# 17_FLOW_Sensor.net
KiCad netlist of a schematic drawn in Altium Designer
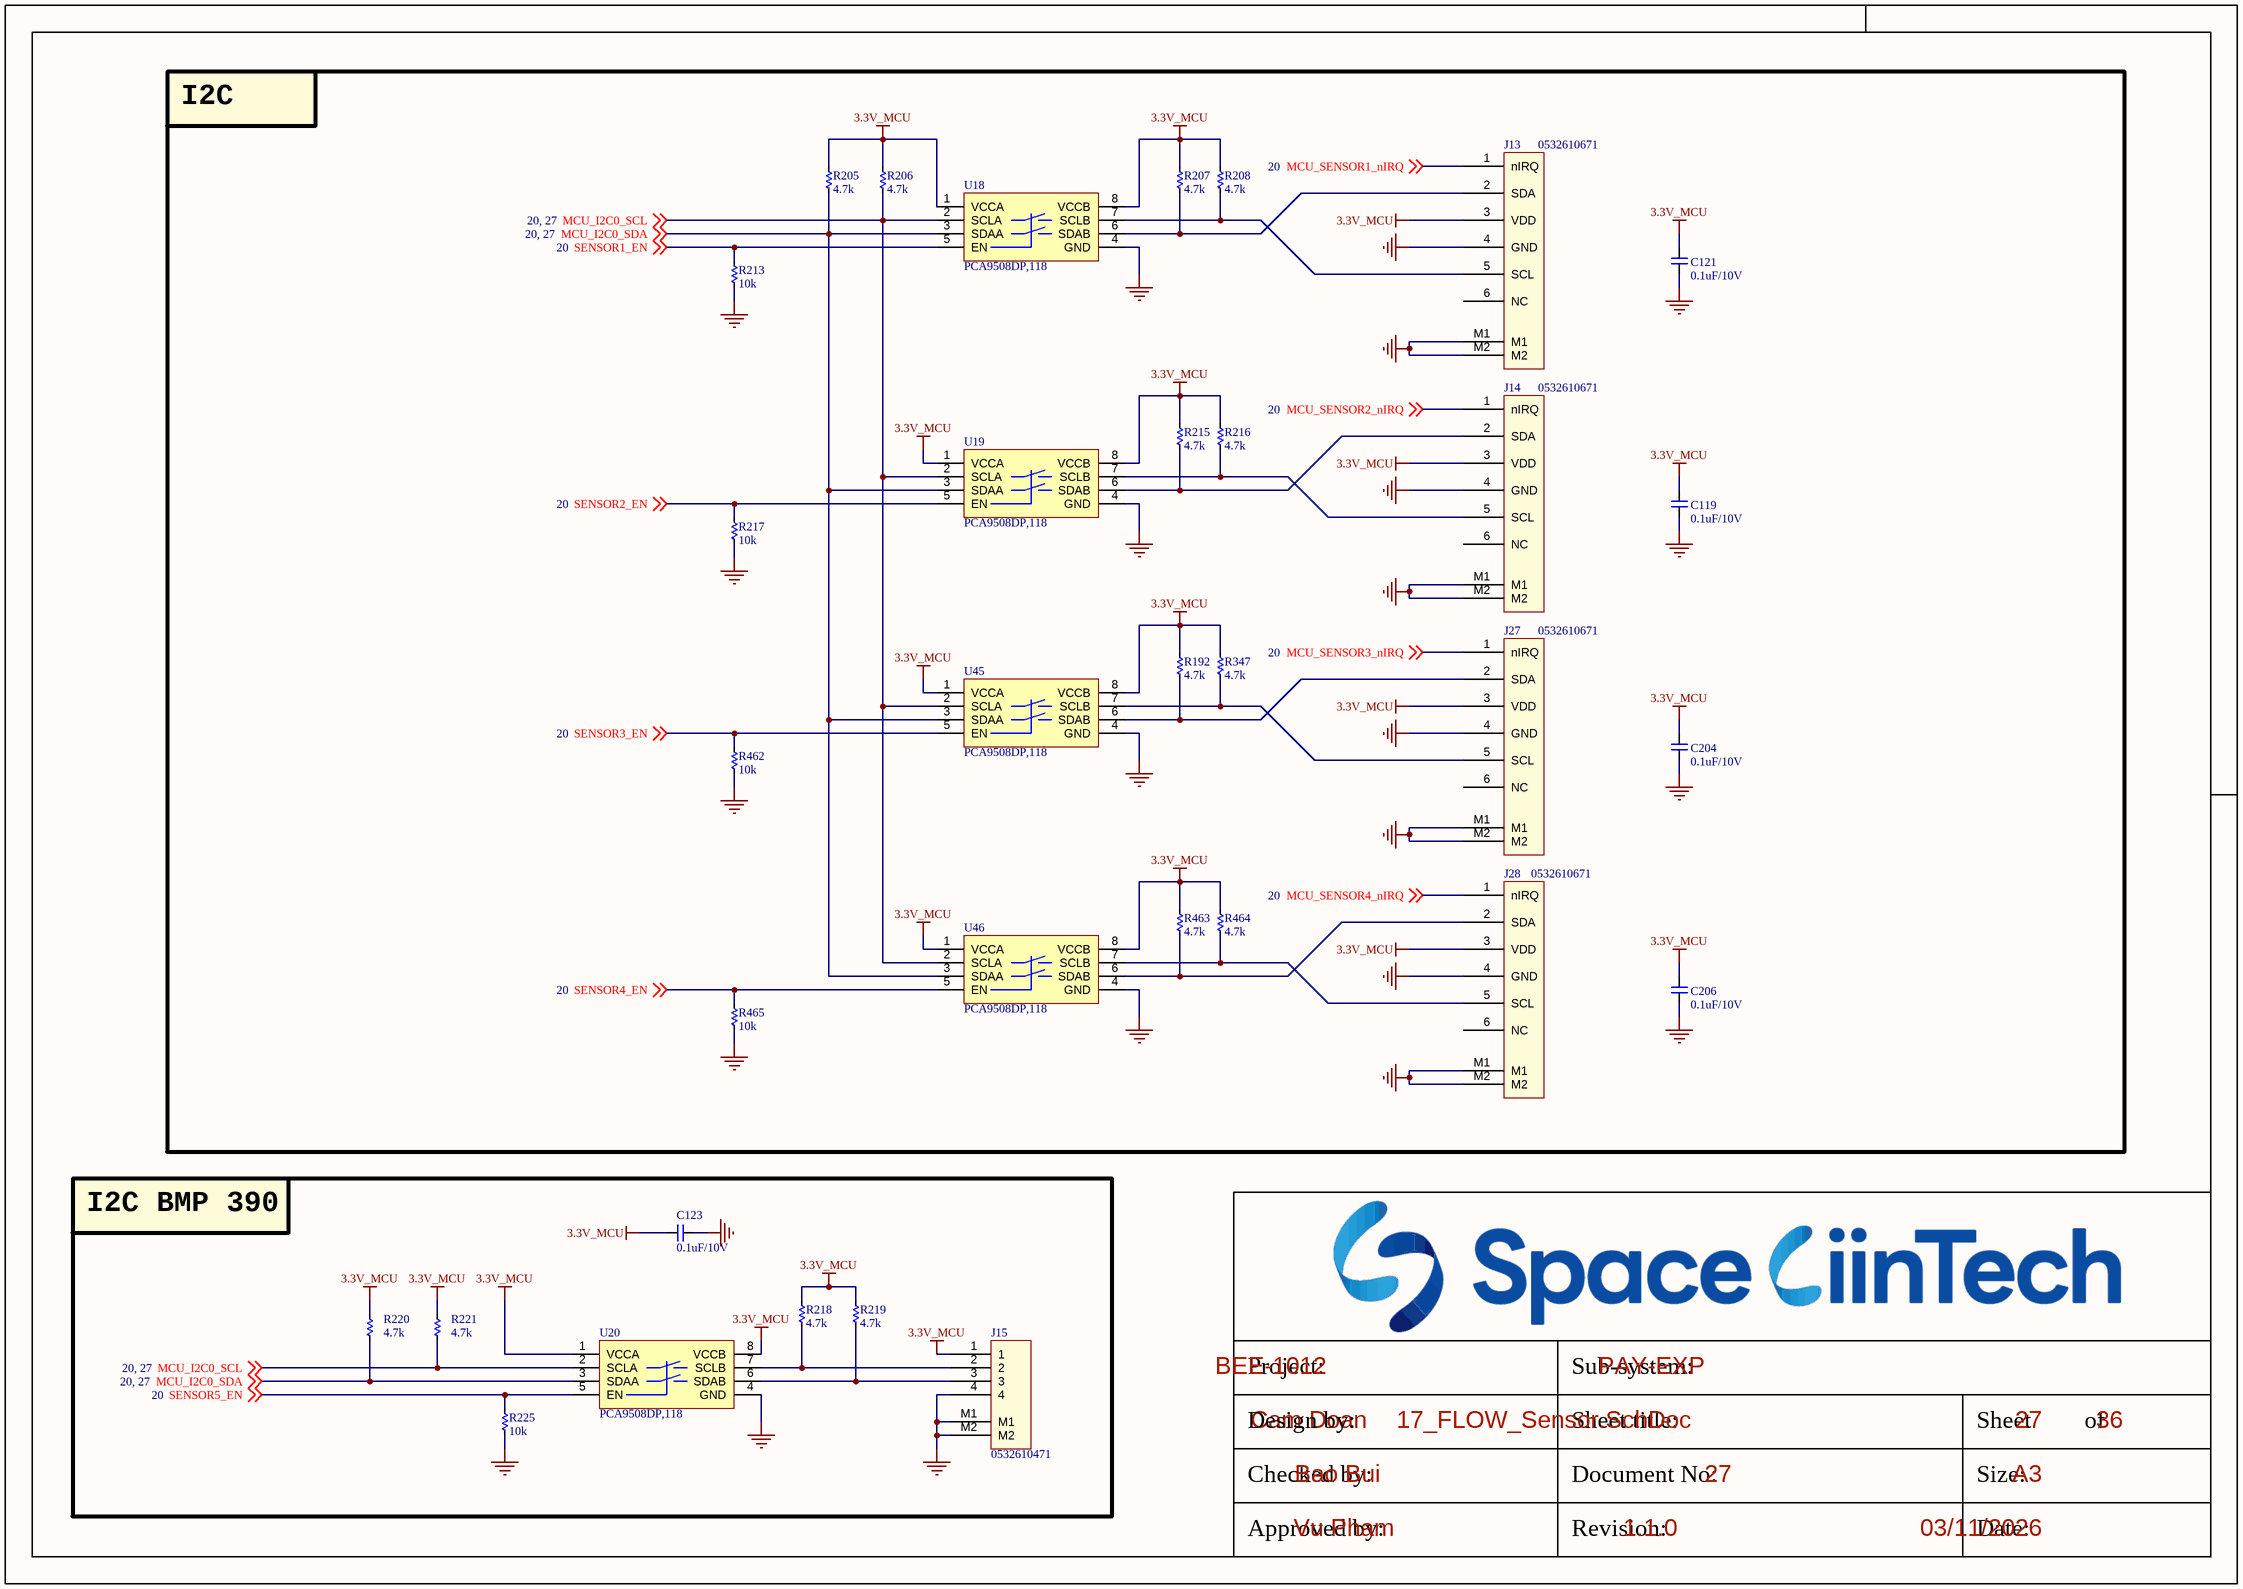
[diagram p0: 17_FLOW_Sensor.SchDoc]

(export (version "E")
  (design (tool "Eeschema 10.0.6"))
  (components
    (comp (ref "C119")
      (value "0.1uF/10V")
      (footprint "CAP_C_1005X60")
      (description "CAP")
      (libsource (lib "LABLIB") (part "_CAP_C_2"))
    )
    (comp (ref "C121")
      (value "0.1uF/10V")
      (footprint "CAP_C_1005X60")
      (description "CAP")
      (libsource (lib "LABLIB") (part "_CAP_C_2"))
    )
    (comp (ref "C123")
      (value "0.1uF/10V")
      (footprint "CAP_C_1005X60")
      (description "CAP")
      (libsource (lib "LABLIB") (part "_CAP_C_2"))
    )
    (comp (ref "C204")
      (value "0.1uF/10V")
      (footprint "CAP_C_1005X60")
      (description "CAP")
      (libsource (lib "LABLIB") (part "_CAP_C_2"))
    )
    (comp (ref "C206")
      (value "0.1uF/10V")
      (footprint "CAP_C_1005X60")
      (description "CAP")
      (libsource (lib "LABLIB") (part "_CAP_C_2"))
    )
    (comp (ref "J13")
      (value "0532610671")
      (footprint "MOLEX_0532610671")
      (libsource (lib "LABLIB") (part "FLOW_SENSOR"))
    )
    (comp (ref "J14")
      (value "0532610671")
      (footprint "MOLEX_0532610671")
      (libsource (lib "LABLIB") (part "FLOW_SENSOR"))
    )
    (comp (ref "J15")
      (value "0532610471")
      (footprint "MOLEX_0532610471")
      (libsource (lib "LABLIB") (part "Header 4x1_2M"))
    )
    (comp (ref "J27")
      (value "0532610671")
      (footprint "MOLEX_0532610671")
      (libsource (lib "LABLIB") (part "FLOW_SENSOR"))
    )
    (comp (ref "J28")
      (value "0532610671")
      (footprint "MOLEX_0532610671")
      (libsource (lib "LABLIB") (part "FLOW_SENSOR"))
    )
    (comp (ref "R192")
      (value "4.7k")
      (footprint "RES_C_1005X40")
      (description "RES")
      (libsource (lib "LABLIB") (part "_RES_B_2"))
    )
    (comp (ref "R205")
      (value "4.7k")
      (footprint "RES_C_1005X40")
      (description "RES")
      (libsource (lib "LABLIB") (part "_RES_B_2"))
    )
    (comp (ref "R206")
      (value "4.7k")
      (footprint "RES_C_1005X40")
      (description "RES")
      (libsource (lib "LABLIB") (part "_RES_B_2"))
    )
    (comp (ref "R207")
      (value "4.7k")
      (footprint "RES_C_1005X40")
      (description "RES")
      (libsource (lib "LABLIB") (part "_RES_B_2"))
    )
    (comp (ref "R208")
      (value "4.7k")
      (footprint "RES_C_1005X40")
      (description "RES")
      (libsource (lib "LABLIB") (part "_RES_B_2"))
    )
    (comp (ref "R213")
      (value "10k")
      (footprint "RES_C_1005X40")
      (description "RES")
      (libsource (lib "LABLIB") (part "_RES_B_2"))
    )
    (comp (ref "R215")
      (value "4.7k")
      (footprint "RES_C_1005X40")
      (description "RES")
      (libsource (lib "LABLIB") (part "_RES_B_2"))
    )
    (comp (ref "R216")
      (value "4.7k")
      (footprint "RES_C_1005X40")
      (description "RES")
      (libsource (lib "LABLIB") (part "_RES_B_2"))
    )
    (comp (ref "R217")
      (value "10k")
      (footprint "RES_C_1005X40")
      (description "RES")
      (libsource (lib "LABLIB") (part "_RES_B_2"))
    )
    (comp (ref "R218")
      (value "4.7k")
      (footprint "RES_C_1005X40")
      (description "RES")
      (libsource (lib "LABLIB") (part "_RES_B_2"))
    )
    (comp (ref "R219")
      (value "4.7k")
      (footprint "RES_C_1005X40")
      (description "RES")
      (libsource (lib "LABLIB") (part "_RES_B_2"))
    )
    (comp (ref "R220")
      (value "4.7k")
      (footprint "RES_C_1005X40")
      (description "RES")
      (libsource (lib "LABLIB") (part "_RES_B_2"))
    )
    (comp (ref "R221")
      (value "4.7k")
      (footprint "RES_C_1005X40")
      (description "RES")
      (libsource (lib "LABLIB") (part "_RES_B_2"))
    )
    (comp (ref "R225")
      (value "10k")
      (footprint "RES_C_1005X40")
      (description "RES")
      (libsource (lib "LABLIB") (part "_RES_B_2"))
    )
    (comp (ref "R347")
      (value "4.7k")
      (footprint "RES_C_1005X40")
      (description "RES")
      (libsource (lib "LABLIB") (part "_RES_B_2"))
    )
    (comp (ref "R462")
      (value "10k")
      (footprint "RES_C_1005X40")
      (description "RES")
      (libsource (lib "LABLIB") (part "_RES_B_2"))
    )
    (comp (ref "R463")
      (value "4.7k")
      (footprint "RES_C_1005X40")
      (description "RES")
      (libsource (lib "LABLIB") (part "_RES_B_2"))
    )
    (comp (ref "R464")
      (value "4.7k")
      (footprint "RES_C_1005X40")
      (description "RES")
      (libsource (lib "LABLIB") (part "_RES_B_2"))
    )
    (comp (ref "R465")
      (value "10k")
      (footprint "RES_C_1005X40")
      (description "RES")
      (libsource (lib "LABLIB") (part "_RES_B_2"))
    )
    (comp (ref "U18")
      (value "PCA9508DP,118")
      (footprint "TSOP8")
      (libsource (lib "EXP_HW_V3") (part "PCA9508DP,118"))
    )
    (comp (ref "U19")
      (value "PCA9508DP,118")
      (footprint "TSOP8")
      (libsource (lib "EXP_HW_V3") (part "PCA9508DP,118"))
    )
    (comp (ref "U20")
      (value "PCA9508DP,118")
      (footprint "TSOP8")
      (libsource (lib "EXP_HW_V3") (part "PCA9508DP,118"))
    )
    (comp (ref "U45")
      (value "PCA9508DP,118")
      (footprint "TSOP8")
      (libsource (lib "EXP_HW_V3") (part "PCA9508DP,118"))
    )
    (comp (ref "U46")
      (value "PCA9508DP,118")
      (footprint "TSOP8")
      (libsource (lib "EXP_HW_V3") (part "PCA9508DP,118"))
    )
  )
  (nets
    (net (code "1") (name "3.3V_MCU") (class "Default")
      (node (ref "C119") (pin "2") (pinfunction "2_2") (pintype "passive"))
      (node (ref "C121") (pin "2") (pinfunction "2_2") (pintype "passive"))
      (node (ref "C123") (pin "2") (pinfunction "2_2") (pintype "passive"))
      (node (ref "C204") (pin "2") (pinfunction "2_2") (pintype "passive"))
      (node (ref "C206") (pin "2") (pinfunction "2_2") (pintype "passive"))
      (node (ref "J13") (pin "3") (pinfunction "VDD_3") (pintype "passive"))
      (node (ref "J14") (pin "3") (pinfunction "VDD_3") (pintype "passive"))
      (node (ref "J15") (pin "1") (pinfunction "1_1") (pintype "passive"))
      (node (ref "J27") (pin "3") (pinfunction "VDD_3") (pintype "passive"))
      (node (ref "J28") (pin "3") (pinfunction "VDD_3") (pintype "passive"))
      (node (ref "R192") (pin "1") (pinfunction "1_1") (pintype "passive"))
      (node (ref "R205") (pin "1") (pinfunction "1_1") (pintype "passive"))
      (node (ref "R206") (pin "1") (pinfunction "1_1") (pintype "passive"))
      (node (ref "R207") (pin "1") (pinfunction "1_1") (pintype "passive"))
      (node (ref "R208") (pin "1") (pinfunction "1_1") (pintype "passive"))
      (node (ref "R215") (pin "1") (pinfunction "1_1") (pintype "passive"))
      (node (ref "R216") (pin "1") (pinfunction "1_1") (pintype "passive"))
      (node (ref "R218") (pin "1") (pinfunction "1_1") (pintype "passive"))
      (node (ref "R219") (pin "1") (pinfunction "1_1") (pintype "passive"))
      (node (ref "R220") (pin "1") (pinfunction "1_1") (pintype "passive"))
      (node (ref "R221") (pin "1") (pinfunction "1_1") (pintype "passive"))
      (node (ref "R347") (pin "1") (pinfunction "1_1") (pintype "passive"))
      (node (ref "R463") (pin "1") (pinfunction "1_1") (pintype "passive"))
      (node (ref "R464") (pin "1") (pinfunction "1_1") (pintype "passive"))
      (node (ref "U18") (pin "1") (pinfunction "VCCA_1") (pintype "passive"))
      (node (ref "U18") (pin "8") (pinfunction "VCCB_8") (pintype "passive"))
      (node (ref "U19") (pin "1") (pinfunction "VCCA_1") (pintype "passive"))
      (node (ref "U19") (pin "8") (pinfunction "VCCB_8") (pintype "passive"))
      (node (ref "U20") (pin "1") (pinfunction "VCCA_1") (pintype "passive"))
      (node (ref "U20") (pin "8") (pinfunction "VCCB_8") (pintype "passive"))
      (node (ref "U45") (pin "1") (pinfunction "VCCA_1") (pintype "passive"))
      (node (ref "U45") (pin "8") (pinfunction "VCCB_8") (pintype "passive"))
      (node (ref "U46") (pin "1") (pinfunction "VCCA_1") (pintype "passive"))
      (node (ref "U46") (pin "8") (pinfunction "VCCB_8") (pintype "passive"))
    )
    (net (code "2") (name "GND") (class "Default")
      (node (ref "C119") (pin "1") (pinfunction "1_1") (pintype "passive"))
      (node (ref "C121") (pin "1") (pinfunction "1_1") (pintype "passive"))
      (node (ref "C123") (pin "1") (pinfunction "1_1") (pintype "passive"))
      (node (ref "C204") (pin "1") (pinfunction "1_1") (pintype "passive"))
      (node (ref "C206") (pin "1") (pinfunction "1_1") (pintype "passive"))
      (node (ref "J13") (pin "4") (pinfunction "GND_4") (pintype "passive"))
      (node (ref "J13") (pin "M1") (pinfunction "M1_M1") (pintype "passive"))
      (node (ref "J13") (pin "M2") (pinfunction "M2_M2") (pintype "passive"))
      (node (ref "J14") (pin "4") (pinfunction "GND_4") (pintype "passive"))
      (node (ref "J14") (pin "M1") (pinfunction "M1_M1") (pintype "passive"))
      (node (ref "J14") (pin "M2") (pinfunction "M2_M2") (pintype "passive"))
      (node (ref "J15") (pin "4") (pinfunction "4_4") (pintype "passive"))
      (node (ref "J15") (pin "M1") (pinfunction "M1_M1") (pintype "passive"))
      (node (ref "J15") (pin "M2") (pinfunction "M2_M2") (pintype "passive"))
      (node (ref "J27") (pin "4") (pinfunction "GND_4") (pintype "passive"))
      (node (ref "J27") (pin "M1") (pinfunction "M1_M1") (pintype "passive"))
      (node (ref "J27") (pin "M2") (pinfunction "M2_M2") (pintype "passive"))
      (node (ref "J28") (pin "4") (pinfunction "GND_4") (pintype "passive"))
      (node (ref "J28") (pin "M1") (pinfunction "M1_M1") (pintype "passive"))
      (node (ref "J28") (pin "M2") (pinfunction "M2_M2") (pintype "passive"))
      (node (ref "R213") (pin "2") (pinfunction "2_2") (pintype "passive"))
      (node (ref "R217") (pin "2") (pinfunction "2_2") (pintype "passive"))
      (node (ref "R225") (pin "2") (pinfunction "2_2") (pintype "passive"))
      (node (ref "R462") (pin "2") (pinfunction "2_2") (pintype "passive"))
      (node (ref "R465") (pin "2") (pinfunction "2_2") (pintype "passive"))
      (node (ref "U18") (pin "4") (pinfunction "GND_4") (pintype "passive"))
      (node (ref "U19") (pin "4") (pinfunction "GND_4") (pintype "passive"))
      (node (ref "U20") (pin "4") (pinfunction "GND_4") (pintype "passive"))
      (node (ref "U45") (pin "4") (pinfunction "GND_4") (pintype "passive"))
      (node (ref "U46") (pin "4") (pinfunction "GND_4") (pintype "passive"))
    )
    (net (code "3") (name "MCU_I2C0_SCL") (class "Default")
      (node (ref "R206") (pin "2") (pinfunction "2_2") (pintype "passive"))
      (node (ref "R221") (pin "2") (pinfunction "2_2") (pintype "passive"))
      (node (ref "U18") (pin "2") (pinfunction "SCLA_2") (pintype "passive"))
      (node (ref "U19") (pin "2") (pinfunction "SCLA_2") (pintype "passive"))
      (node (ref "U20") (pin "2") (pinfunction "SCLA_2") (pintype "passive"))
      (node (ref "U45") (pin "2") (pinfunction "SCLA_2") (pintype "passive"))
      (node (ref "U46") (pin "2") (pinfunction "SCLA_2") (pintype "passive"))
    )
    (net (code "4") (name "MCU_I2C0_SDA") (class "Default")
      (node (ref "R205") (pin "2") (pinfunction "2_2") (pintype "passive"))
      (node (ref "R220") (pin "2") (pinfunction "2_2") (pintype "passive"))
      (node (ref "U18") (pin "3") (pinfunction "SDAA_3") (pintype "passive"))
      (node (ref "U19") (pin "3") (pinfunction "SDAA_3") (pintype "passive"))
      (node (ref "U20") (pin "3") (pinfunction "SDAA_3") (pintype "passive"))
      (node (ref "U45") (pin "3") (pinfunction "SDAA_3") (pintype "passive"))
      (node (ref "U46") (pin "3") (pinfunction "SDAA_3") (pintype "passive"))
    )
    (net (code "5") (name "MCU_SENSOR1_nIRQ") (class "Default")
      (node (ref "J13") (pin "1") (pinfunction "nIRQ_1") (pintype "passive"))
    )
    (net (code "6") (name "MCU_SENSOR2_nIRQ") (class "Default")
      (node (ref "J14") (pin "1") (pinfunction "nIRQ_1") (pintype "passive"))
    )
    (net (code "7") (name "MCU_SENSOR3_nIRQ") (class "Default")
      (node (ref "J27") (pin "1") (pinfunction "nIRQ_1") (pintype "passive"))
    )
    (net (code "8") (name "MCU_SENSOR4_nIRQ") (class "Default")
      (node (ref "J28") (pin "1") (pinfunction "nIRQ_1") (pintype "passive"))
    )
    (net (code "9") (name "Net-(J13-SCL)") (class "Default")
      (node (ref "J13") (pin "5") (pinfunction "SCL_5") (pintype "passive"))
      (node (ref "R208") (pin "2") (pinfunction "2_2") (pintype "passive"))
      (node (ref "U18") (pin "7") (pinfunction "SCLB_7") (pintype "passive"))
    )
    (net (code "10") (name "Net-(J13-SDA)") (class "Default")
      (node (ref "J13") (pin "2") (pinfunction "SDA_2") (pintype "passive"))
      (node (ref "R207") (pin "2") (pinfunction "2_2") (pintype "passive"))
      (node (ref "U18") (pin "6") (pinfunction "SDAB_6") (pintype "passive"))
    )
    (net (code "11") (name "Net-(J14-SCL)") (class "Default")
      (node (ref "J14") (pin "5") (pinfunction "SCL_5") (pintype "passive"))
      (node (ref "R216") (pin "2") (pinfunction "2_2") (pintype "passive"))
      (node (ref "U19") (pin "7") (pinfunction "SCLB_7") (pintype "passive"))
    )
    (net (code "12") (name "Net-(J14-SDA)") (class "Default")
      (node (ref "J14") (pin "2") (pinfunction "SDA_2") (pintype "passive"))
      (node (ref "R215") (pin "2") (pinfunction "2_2") (pintype "passive"))
      (node (ref "U19") (pin "6") (pinfunction "SDAB_6") (pintype "passive"))
    )
    (net (code "13") (name "Net-(J27-SCL)") (class "Default")
      (node (ref "J27") (pin "5") (pinfunction "SCL_5") (pintype "passive"))
      (node (ref "R347") (pin "2") (pinfunction "2_2") (pintype "passive"))
      (node (ref "U45") (pin "7") (pinfunction "SCLB_7") (pintype "passive"))
    )
    (net (code "14") (name "Net-(J27-SDA)") (class "Default")
      (node (ref "J27") (pin "2") (pinfunction "SDA_2") (pintype "passive"))
      (node (ref "R192") (pin "2") (pinfunction "2_2") (pintype "passive"))
      (node (ref "U45") (pin "6") (pinfunction "SDAB_6") (pintype "passive"))
    )
    (net (code "15") (name "Net-(J28-SCL)") (class "Default")
      (node (ref "J28") (pin "5") (pinfunction "SCL_5") (pintype "passive"))
      (node (ref "R464") (pin "2") (pinfunction "2_2") (pintype "passive"))
      (node (ref "U46") (pin "7") (pinfunction "SCLB_7") (pintype "passive"))
    )
    (net (code "16") (name "Net-(J28-SDA)") (class "Default")
      (node (ref "J28") (pin "2") (pinfunction "SDA_2") (pintype "passive"))
      (node (ref "R463") (pin "2") (pinfunction "2_2") (pintype "passive"))
      (node (ref "U46") (pin "6") (pinfunction "SDAB_6") (pintype "passive"))
    )
    (net (code "17") (name "Net-(U20-SCLB)") (class "Default")
      (node (ref "J15") (pin "2") (pinfunction "2_2") (pintype "passive"))
      (node (ref "R218") (pin "2") (pinfunction "2_2") (pintype "passive"))
      (node (ref "U20") (pin "7") (pinfunction "SCLB_7") (pintype "passive"))
    )
    (net (code "18") (name "Net-(U20-SDAB)") (class "Default")
      (node (ref "J15") (pin "3") (pinfunction "3_3") (pintype "passive"))
      (node (ref "R219") (pin "2") (pinfunction "2_2") (pintype "passive"))
      (node (ref "U20") (pin "6") (pinfunction "SDAB_6") (pintype "passive"))
    )
    (net (code "19") (name "SENSOR1_EN") (class "Default")
      (node (ref "R213") (pin "1") (pinfunction "1_1") (pintype "passive"))
      (node (ref "U18") (pin "5") (pinfunction "EN_5") (pintype "passive"))
    )
    (net (code "20") (name "SENSOR2_EN") (class "Default")
      (node (ref "R217") (pin "1") (pinfunction "1_1") (pintype "passive"))
      (node (ref "U19") (pin "5") (pinfunction "EN_5") (pintype "passive"))
    )
    (net (code "21") (name "SENSOR3_EN") (class "Default")
      (node (ref "R462") (pin "1") (pinfunction "1_1") (pintype "passive"))
      (node (ref "U45") (pin "5") (pinfunction "EN_5") (pintype "passive"))
    )
    (net (code "22") (name "SENSOR4_EN") (class "Default")
      (node (ref "R465") (pin "1") (pinfunction "1_1") (pintype "passive"))
      (node (ref "U46") (pin "5") (pinfunction "EN_5") (pintype "passive"))
    )
    (net (code "23") (name "SENSOR5_EN") (class "Default")
      (node (ref "R225") (pin "1") (pinfunction "1_1") (pintype "passive"))
      (node (ref "U20") (pin "5") (pinfunction "EN_5") (pintype "passive"))
    )
    (net (code "24") (name "unconnected-(J13-NC-Pad6)") (class "Default")
      (node (ref "J13") (pin "6") (pinfunction "NC_6") (pintype "passive"))
    )
    (net (code "25") (name "unconnected-(J14-NC-Pad6)") (class "Default")
      (node (ref "J14") (pin "6") (pinfunction "NC_6") (pintype "passive"))
    )
    (net (code "26") (name "unconnected-(J27-NC-Pad6)") (class "Default")
      (node (ref "J27") (pin "6") (pinfunction "NC_6") (pintype "passive"))
    )
    (net (code "27") (name "unconnected-(J28-NC-Pad6)") (class "Default")
      (node (ref "J28") (pin "6") (pinfunction "NC_6") (pintype "passive"))
    )
  )
)
